# satshakit_laser.net
KiCad netlist of a schematic drawn in EAGLE
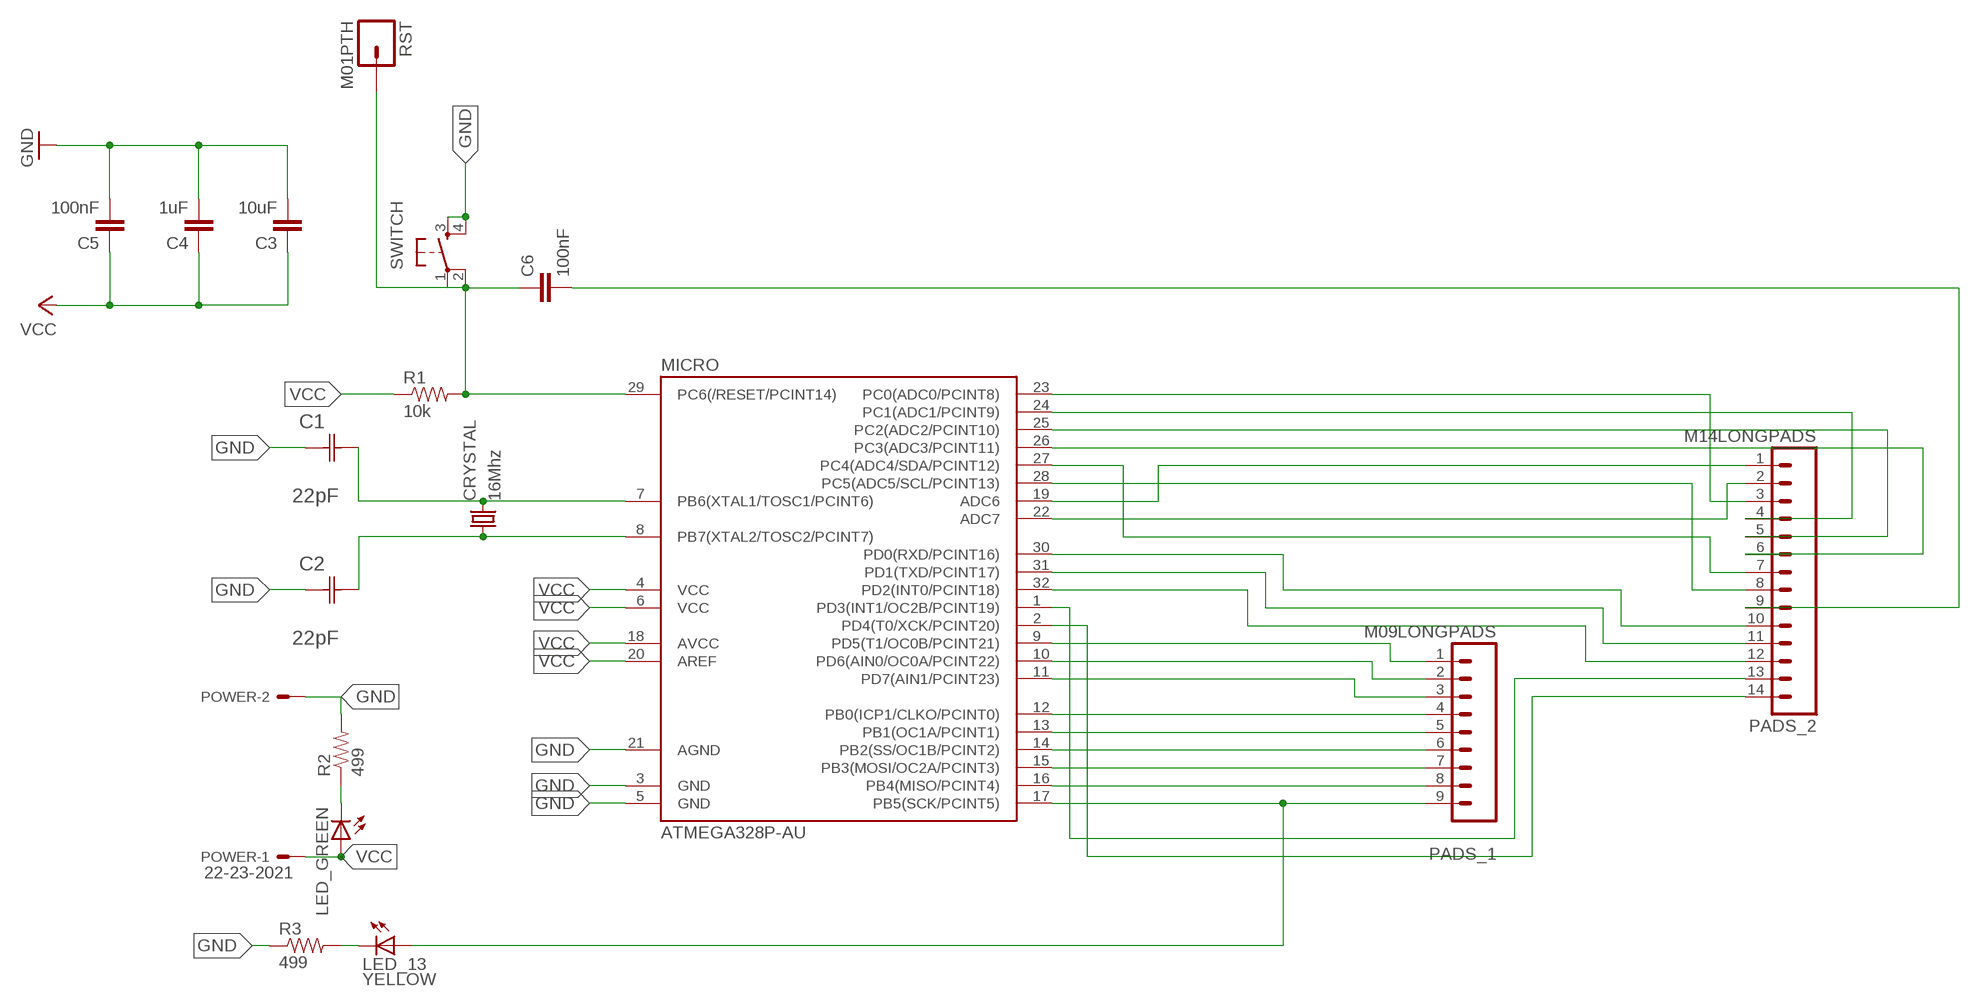
[diagram p0: schematic, sheet 1]

(export (version "E")
  (design (tool "Eeschema 10.0.6"))
  (components
    (comp (ref "C1")
      (value "22pF")
      (footprint "eagle-import:CAPC3216X178N")
      (fields (field (name "MPN") "0612ZC225MAT2A") (field (name "TOLERANCE") "±20%"))
      (libsource (lib "eagle-import") (part "0612ZC225MAT2A"))
    )
    (comp (ref "C2")
      (value "22pF")
      (footprint "eagle-import:CAPC3216X178N")
      (fields (field (name "MPN") "0612ZC225MAT2A") (field (name "TOLERANCE") "±20%"))
      (libsource (lib "eagle-import") (part "0612ZC225MAT2A"))
    )
    (comp (ref "C3")
      (value "10uF")
      (footprint "eagle-import:1206")
      (libsource (lib "eagle-import") (part "CAP1206"))
    )
    (comp (ref "C4")
      (value "1uF")
      (footprint "eagle-import:1206")
      (libsource (lib "eagle-import") (part "CAP1206"))
    )
    (comp (ref "C5")
      (value "100nF")
      (footprint "eagle-import:1206")
      (libsource (lib "eagle-import") (part "CAP1206"))
    )
    (comp (ref "C6")
      (value "100nF")
      (footprint "eagle-import:1206")
      (libsource (lib "eagle-import") (part "CAP1206"))
    )
    (comp (ref "CRYSTAL")
      (value "16Mhz")
      (footprint "eagle-import:CSM-7X-DU")
      (libsource (lib "eagle-import") (part "CSM-7X-DU"))
    )
    (comp (ref "LED_13")
      (value "YELLOW")
      (footprint "eagle-import:1206")
      (libsource (lib "eagle-import") (part "LED1206"))
    )
    (comp (ref "LED_GREEN")
      (value "LED1206")
      (footprint "eagle-import:1206")
      (libsource (lib "eagle-import") (part "LED1206"))
    )
    (comp (ref "MICRO")
      (value "ATMEGA328P-AU")
      (footprint "eagle-import:TQFP32-08")
      (libsource (lib "eagle-import") (part "ATMEGA48/88/168-AU"))
    )
    (comp (ref "PADS_1")
      (value "M09LONGPADS")
      (footprint "eagle-import:1X09_LONGPADS")
      (libsource (lib "eagle-import") (part "M09LONGPADS"))
    )
    (comp (ref "PADS_2")
      (value "M14LONGPADS")
      (footprint "eagle-import:1X14-LONGPADS")
      (libsource (lib "eagle-import") (part "M14LONGPADS"))
    )
    (comp (ref "POWER")
      (value "22-23-2021")
      (footprint "eagle-import:22-23-2021")
      (fields (field (name "MF") "MOLEX"))
      (libsource (lib "eagle-import") (part "22-23-2021"))
    )
    (comp (ref "R1")
      (value "10k")
      (footprint "eagle-import:1206")
      (libsource (lib "eagle-import") (part "RESISTOR1206"))
    )
    (comp (ref "R2")
      (value "499")
      (footprint "eagle-import:1206")
      (libsource (lib "eagle-import") (part "RESISTOR1206"))
    )
    (comp (ref "R3")
      (value "499")
      (footprint "eagle-import:1206")
      (libsource (lib "eagle-import") (part "RESISTOR1206"))
    )
    (comp (ref "RST")
      (value "M01PTH")
      (footprint "eagle-import:1X01")
      (libsource (lib "eagle-import") (part "M01PTH"))
    )
    (comp (ref "SWITCH")
      (value "6MM_SWITCH6MM_SWITCH")
      (footprint "eagle-import:6MM_SWITCH")
      (libsource (lib "eagle-import") (part "6MM_SWITCH6MM_SWITCH"))
    )
  )
  (nets
    (net (code "1") (name "GND") (class "Default")
      (node (ref "C1") (pin "1") (pinfunction "C1_1") (pintype "passive"))
      (node (ref "C2") (pin "1") (pinfunction "C1_1") (pintype "passive"))
      (node (ref "C3") (pin "2") (pinfunction "2_2") (pintype "passive"))
      (node (ref "C4") (pin "2") (pinfunction "2_2") (pintype "passive"))
      (node (ref "C5") (pin "2") (pinfunction "2_2") (pintype "passive"))
      (node (ref "MICRO") (pin "21") (pinfunction "AGND_21") (pintype "power_in"))
      (node (ref "MICRO") (pin "3") (pinfunction "GND_3") (pintype "power_in"))
      (node (ref "MICRO") (pin "5") (pinfunction "GND_5") (pintype "power_in"))
      (node (ref "POWER") (pin "2") (pinfunction "S_2") (pintype "passive"))
      (node (ref "R2") (pin "2") (pinfunction "2_2") (pintype "passive"))
      (node (ref "R3") (pin "1") (pinfunction "1_1") (pintype "passive"))
      (node (ref "SWITCH") (pin "3") (pinfunction "S_3") (pintype "passive"))
      (node (ref "SWITCH") (pin "4") (pinfunction "S1_4") (pintype "passive"))
    )
    (net (code "2") (name "Net-(C1-C2)") (class "Default")
      (node (ref "C1") (pin "2") (pinfunction "C2_2") (pintype "passive"))
      (node (ref "CRYSTAL") (pin "2") (pinfunction "2_2") (pintype "passive"))
      (node (ref "MICRO") (pin "7") (pinfunction "PB6(XTAL1/TOSC1/PCINT6)_7") (pintype "bidirectional"))
    )
    (net (code "3") (name "Net-(C2-C2)") (class "Default")
      (node (ref "C2") (pin "2") (pinfunction "C2_2") (pintype "passive"))
      (node (ref "CRYSTAL") (pin "1") (pinfunction "1_1") (pintype "passive"))
      (node (ref "MICRO") (pin "8") (pinfunction "PB7(XTAL2/TOSC2/PCINT7)_8") (pintype "bidirectional"))
    )
    (net (code "4") (name "Net-(C6-Pad2)") (class "Default")
      (node (ref "C6") (pin "2") (pinfunction "2_2") (pintype "passive"))
      (node (ref "PADS_2") (pin "9") (pinfunction "9_9") (pintype "passive"))
    )
    (net (code "5") (name "Net-(LED_13-A)") (class "Default")
      (node (ref "LED_13") (pin "1") (pinfunction "A_1") (pintype "passive"))
      (node (ref "MICRO") (pin "17") (pinfunction "PB5(SCK/PCINT5)_17") (pintype "bidirectional"))
      (node (ref "PADS_1") (pin "9") (pinfunction "9_9") (pintype "passive"))
    )
    (net (code "6") (name "Net-(LED_13-C)") (class "Default")
      (node (ref "LED_13") (pin "2") (pinfunction "C_2") (pintype "passive"))
      (node (ref "R3") (pin "2") (pinfunction "2_2") (pintype "passive"))
    )
    (net (code "7") (name "Net-(LED_GREEN-C)") (class "Default")
      (node (ref "LED_GREEN") (pin "2") (pinfunction "C_2") (pintype "passive"))
      (node (ref "R2") (pin "1") (pinfunction "1_1") (pintype "passive"))
    )
    (net (code "8") (name "Net-(MICRO-ADC6)") (class "Default")
      (node (ref "MICRO") (pin "19") (pinfunction "ADC6_19") (pintype "passive"))
      (node (ref "PADS_2") (pin "1") (pinfunction "1_1") (pintype "passive"))
    )
    (net (code "9") (name "Net-(MICRO-ADC7)") (class "Default")
      (node (ref "MICRO") (pin "22") (pinfunction "ADC7_22") (pintype "passive"))
      (node (ref "PADS_2") (pin "2") (pinfunction "2_2") (pintype "passive"))
    )
    (net (code "10") (name "Net-(MICRO-PB0(ICP1{slash}CLKO{slash}PCINT0))") (class "Default")
      (node (ref "MICRO") (pin "12") (pinfunction "PB0(ICP1/CLKO/PCINT0)_12") (pintype "bidirectional"))
      (node (ref "PADS_1") (pin "4") (pinfunction "4_4") (pintype "passive"))
    )
    (net (code "11") (name "Net-(MICRO-PB1(OC1A{slash}PCINT1))") (class "Default")
      (node (ref "MICRO") (pin "13") (pinfunction "PB1(OC1A/PCINT1)_13") (pintype "bidirectional"))
      (node (ref "PADS_1") (pin "5") (pinfunction "5_5") (pintype "passive"))
    )
    (net (code "12") (name "Net-(MICRO-PB2(SS{slash}OC1B{slash}PCINT2))") (class "Default")
      (node (ref "MICRO") (pin "14") (pinfunction "PB2(SS/OC1B/PCINT2)_14") (pintype "bidirectional"))
      (node (ref "PADS_1") (pin "6") (pinfunction "6_6") (pintype "passive"))
    )
    (net (code "13") (name "Net-(MICRO-PB3(MOSI{slash}OC2A{slash}PCINT3))") (class "Default")
      (node (ref "MICRO") (pin "15") (pinfunction "PB3(MOSI/OC2A/PCINT3)_15") (pintype "bidirectional"))
      (node (ref "PADS_1") (pin "7") (pinfunction "7_7") (pintype "passive"))
    )
    (net (code "14") (name "Net-(MICRO-PB4(MISO{slash}PCINT4))") (class "Default")
      (node (ref "MICRO") (pin "16") (pinfunction "PB4(MISO/PCINT4)_16") (pintype "bidirectional"))
      (node (ref "PADS_1") (pin "8") (pinfunction "8_8") (pintype "passive"))
    )
    (net (code "15") (name "Net-(MICRO-PC0(ADC0{slash}PCINT8))") (class "Default")
      (node (ref "MICRO") (pin "23") (pinfunction "PC0(ADC0/PCINT8)_23") (pintype "bidirectional"))
      (node (ref "PADS_2") (pin "3") (pinfunction "3_3") (pintype "passive"))
    )
    (net (code "16") (name "Net-(MICRO-PC1(ADC1{slash}PCINT9))") (class "Default")
      (node (ref "MICRO") (pin "24") (pinfunction "PC1(ADC1/PCINT9)_24") (pintype "bidirectional"))
      (node (ref "PADS_2") (pin "4") (pinfunction "4_4") (pintype "passive"))
    )
    (net (code "17") (name "Net-(MICRO-PC2(ADC2{slash}PCINT10))") (class "Default")
      (node (ref "MICRO") (pin "25") (pinfunction "PC2(ADC2/PCINT10)_25") (pintype "bidirectional"))
      (node (ref "PADS_2") (pin "5") (pinfunction "5_5") (pintype "passive"))
    )
    (net (code "18") (name "Net-(MICRO-PC3(ADC3{slash}PCINT11))") (class "Default")
      (node (ref "MICRO") (pin "26") (pinfunction "PC3(ADC3/PCINT11)_26") (pintype "bidirectional"))
      (node (ref "PADS_2") (pin "6") (pinfunction "6_6") (pintype "passive"))
    )
    (net (code "19") (name "Net-(MICRO-PC4(ADC4{slash}SDA{slash}PCINT12))") (class "Default")
      (node (ref "MICRO") (pin "27") (pinfunction "PC4(ADC4/SDA/PCINT12)_27") (pintype "bidirectional"))
      (node (ref "PADS_2") (pin "7") (pinfunction "7_7") (pintype "passive"))
    )
    (net (code "20") (name "Net-(MICRO-PC5(ADC5{slash}SCL{slash}PCINT13))") (class "Default")
      (node (ref "MICRO") (pin "28") (pinfunction "PC5(ADC5/SCL/PCINT13)_28") (pintype "bidirectional"))
      (node (ref "PADS_2") (pin "8") (pinfunction "8_8") (pintype "passive"))
    )
    (net (code "21") (name "Net-(MICRO-PC6({slash}RESET{slash}PCINT14))") (class "Default")
      (node (ref "C6") (pin "1") (pinfunction "1_1") (pintype "passive"))
      (node (ref "MICRO") (pin "29") (pinfunction "PC6(/RESET/PCINT14)_29") (pintype "bidirectional"))
      (node (ref "R1") (pin "2") (pinfunction "2_2") (pintype "passive"))
      (node (ref "RST") (pin "1") (pinfunction "1_1") (pintype "passive"))
      (node (ref "SWITCH") (pin "1") (pinfunction "P_1") (pintype "passive"))
      (node (ref "SWITCH") (pin "2") (pinfunction "P1_2") (pintype "passive"))
    )
    (net (code "22") (name "Net-(MICRO-PD0(RXD{slash}PCINT16))") (class "Default")
      (node (ref "MICRO") (pin "30") (pinfunction "PD0(RXD/PCINT16)_30") (pintype "bidirectional"))
      (node (ref "PADS_2") (pin "10") (pinfunction "10_10") (pintype "passive"))
    )
    (net (code "23") (name "Net-(MICRO-PD1(TXD{slash}PCINT17))") (class "Default")
      (node (ref "MICRO") (pin "31") (pinfunction "PD1(TXD/PCINT17)_31") (pintype "bidirectional"))
      (node (ref "PADS_2") (pin "11") (pinfunction "11_11") (pintype "passive"))
    )
    (net (code "24") (name "Net-(MICRO-PD2(INT0{slash}PCINT18))") (class "Default")
      (node (ref "MICRO") (pin "32") (pinfunction "PD2(INT0/PCINT18)_32") (pintype "bidirectional"))
      (node (ref "PADS_2") (pin "12") (pinfunction "12_12") (pintype "passive"))
    )
    (net (code "25") (name "Net-(MICRO-PD3(INT1{slash}OC2B{slash}PCINT19))") (class "Default")
      (node (ref "MICRO") (pin "1") (pinfunction "PD3(INT1/OC2B/PCINT19)_1") (pintype "bidirectional"))
      (node (ref "PADS_2") (pin "13") (pinfunction "13_13") (pintype "passive"))
    )
    (net (code "26") (name "Net-(MICRO-PD4(T0{slash}XCK{slash}PCINT20))") (class "Default")
      (node (ref "MICRO") (pin "2") (pinfunction "PD4(T0/XCK/PCINT20)_2") (pintype "bidirectional"))
      (node (ref "PADS_2") (pin "14") (pinfunction "14_14") (pintype "passive"))
    )
    (net (code "27") (name "Net-(MICRO-PD5(T1{slash}OC0B{slash}PCINT21))") (class "Default")
      (node (ref "MICRO") (pin "9") (pinfunction "PD5(T1/OC0B/PCINT21)_9") (pintype "bidirectional"))
      (node (ref "PADS_1") (pin "1") (pinfunction "1_1") (pintype "passive"))
    )
    (net (code "28") (name "Net-(MICRO-PD6(AIN0{slash}OC0A{slash}PCINT22))") (class "Default")
      (node (ref "MICRO") (pin "10") (pinfunction "PD6(AIN0/OC0A/PCINT22)_10") (pintype "bidirectional"))
      (node (ref "PADS_1") (pin "2") (pinfunction "2_2") (pintype "passive"))
    )
    (net (code "29") (name "Net-(MICRO-PD7(AIN1{slash}PCINT23))") (class "Default")
      (node (ref "MICRO") (pin "11") (pinfunction "PD7(AIN1/PCINT23)_11") (pintype "bidirectional"))
      (node (ref "PADS_1") (pin "3") (pinfunction "3_3") (pintype "passive"))
    )
    (net (code "30") (name "VCC") (class "Default")
      (node (ref "C3") (pin "1") (pinfunction "1_1") (pintype "passive"))
      (node (ref "C4") (pin "1") (pinfunction "1_1") (pintype "passive"))
      (node (ref "C5") (pin "1") (pinfunction "1_1") (pintype "passive"))
      (node (ref "LED_GREEN") (pin "1") (pinfunction "A_1") (pintype "passive"))
      (node (ref "MICRO") (pin "18") (pinfunction "AVCC_18") (pintype "passive"))
      (node (ref "MICRO") (pin "20") (pinfunction "AREF_20") (pintype "passive"))
      (node (ref "MICRO") (pin "4") (pinfunction "VCC_4") (pintype "power_in"))
      (node (ref "MICRO") (pin "6") (pinfunction "VCC_6") (pintype "power_in"))
      (node (ref "POWER") (pin "1") (pinfunction "S_1") (pintype "passive"))
      (node (ref "R1") (pin "1") (pinfunction "1_1") (pintype "passive"))
    )
  )
)
